# esp-node.net
KiCad netlist of a schematic drawn in Altium Designer
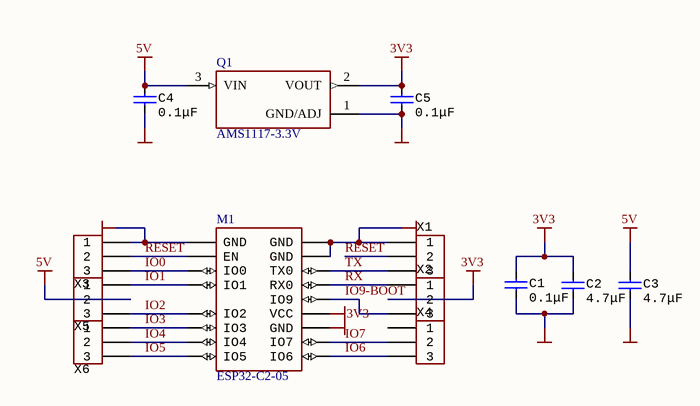
[diagram p0: esp-node.SchDoc]

(export (version "E")
  (design (tool "Eeschema 10.0.6"))
  (components
    (comp (ref "C1")
      (value "0.1μF")
      (footprint "CAP: 0603")
      (description "0.1uF, 100V, 0603, X7R, ±10%, -55...+125°C")
      (fields (field (name "MANUFACTURER") "Samsung") (field (name "PARTNUMBER") "CL10B104KC8NNNC"))
      (libsource (lib "capacitor") (part "CL10B104KC8NNNC"))
    )
    (comp (ref "C2")
      (value "4.7μF")
      (footprint "CAP: 0603")
      (description "4.7uF, 6.3V, 0603, X7R, ±20%, -55...+85°C")
      (fields (field (name "PARTNUMBER") "CL10B475KQ8NQNC") (field (name "MANUFACTURER") "Samsung"))
      (libsource (lib "capacitor") (part "CL10B475KQ8NQNC"))
    )
    (comp (ref "C3")
      (value "4.7μF")
      (footprint "CAP: 0603")
      (description "4.7uF, 6.3V, 0603, X7R, ±20%, -55...+85°C")
      (fields (field (name "PARTNUMBER") "CL10B475KQ8NQNC") (field (name "MANUFACTURER") "Samsung"))
      (libsource (lib "capacitor") (part "CL10B475KQ8NQNC"))
    )
    (comp (ref "C4")
      (value "0.1μF")
      (footprint "CAP: 0603")
      (description "0.1uF, 100V, 0603, X7R, ±10%, -55...+125°C")
      (fields (field (name "MANUFACTURER") "Samsung") (field (name "PARTNUMBER") "CL10B104KC8NNNC"))
      (libsource (lib "capacitor") (part "CL10B104KC8NNNC"))
    )
    (comp (ref "C5")
      (value "0.1μF")
      (footprint "CAP: 0603")
      (description "0.1uF, 100V, 0603, X7R, ±10%, -55...+125°C")
      (fields (field (name "MANUFACTURER") "Samsung") (field (name "PARTNUMBER") "CL10B104KC8NNNC"))
      (libsource (lib "capacitor") (part "CL10B104KC8NNNC"))
    )
    (comp (ref "M1")
      (value "ESP32-C2-05")
      (footprint "ESP32-C2-05")
      (libsource (lib "ic-mcu-dsp") (part "ESP32-C2-05"))
    )
    (comp (ref "Q1")
      (value "AMS1117-3.3V")
      (footprint "SOT223")
      (libsource (lib "ic-power-supply") (part "AMS1117-3.3V"))
    )
    (comp (ref "X1")
      (value "PMbus")
      (footprint "footprint:CON: PLS-3")
      (description "3 pins, pitch 2.54 mm, 500VAC, 2A/pin, -40...+85°C")
      (fields (field (name "MANUFACTURER") "Connfly") (field (name "PARTNUMBER") "PLS-3"))
      (libsource (lib "") (part "PLS-3_1"))
    )
    (comp (ref "X2")
      (value "PMbus")
      (footprint "footprint:CON: PLS-3")
      (description "3 pins, pitch 2.54 mm, 500VAC, 2A/pin, -40...+85°C")
      (fields (field (name "MANUFACTURER") "Connfly") (field (name "PARTNUMBER") "PLS-3"))
      (libsource (lib "") (part "PLS-3_1"))
    )
    (comp (ref "X3")
      (value "PMbus")
      (footprint "footprint:CON: PLS-3")
      (description "3 pins, pitch 2.54 mm, 500VAC, 2A/pin, -40...+85°C")
      (fields (field (name "MANUFACTURER") "Connfly") (field (name "PARTNUMBER") "PLS-3"))
      (libsource (lib "connector") (part "PLS-3"))
    )
    (comp (ref "X4")
      (value "PMbus")
      (footprint "footprint:CON: PLS-3")
      (description "3 pins, pitch 2.54 mm, 500VAC, 2A/pin, -40...+85°C")
      (fields (field (name "MANUFACTURER") "Connfly") (field (name "PARTNUMBER") "PLS-3"))
      (libsource (lib "") (part "PLS-3_1"))
    )
    (comp (ref "X5")
      (value "PMbus")
      (footprint "footprint:CON: PLS-3")
      (description "3 pins, pitch 2.54 mm, 500VAC, 2A/pin, -40...+85°C")
      (fields (field (name "MANUFACTURER") "Connfly") (field (name "PARTNUMBER") "PLS-3"))
      (libsource (lib "connector") (part "PLS-3"))
    )
    (comp (ref "X6")
      (value "PMbus")
      (footprint "footprint:CON: PLS-3")
      (description "3 pins, pitch 2.54 mm, 500VAC, 2A/pin, -40...+85°C")
      (fields (field (name "MANUFACTURER") "Connfly") (field (name "PARTNUMBER") "PLS-3"))
      (libsource (lib "connector") (part "PLS-3"))
    )
  )
  (nets
    (net (code "1") (name "/IO0") (class "Default")
      (node (ref "M1") (pin "3") (pinfunction "IO0_3") (pintype "bidirectional"))
      (node (ref "X3") (pin "3") (pinfunction "3_3") (pintype "power_in"))
    )
    (net (code "2") (name "/IO1") (class "Default")
      (node (ref "M1") (pin "4") (pinfunction "IO1_4") (pintype "bidirectional"))
      (node (ref "X5") (pin "1") (pinfunction "1_1") (pintype "passive"))
    )
    (net (code "3") (name "/IO2") (class "Default")
      (node (ref "M1") (pin "5") (pinfunction "IO2_5") (pintype "bidirectional"))
      (node (ref "X5") (pin "3") (pinfunction "3_3") (pintype "power_in"))
    )
    (net (code "4") (name "/IO3") (class "Default")
      (node (ref "M1") (pin "6") (pinfunction "IO3_6") (pintype "bidirectional"))
      (node (ref "X6") (pin "1") (pinfunction "1_1") (pintype "passive"))
    )
    (net (code "5") (name "/IO4") (class "Default")
      (node (ref "M1") (pin "7") (pinfunction "IO4_7") (pintype "bidirectional"))
      (node (ref "X6") (pin "2") (pinfunction "2_2") (pintype "passive"))
    )
    (net (code "6") (name "/IO5") (class "Default")
      (node (ref "M1") (pin "8") (pinfunction "IO5_8") (pintype "bidirectional"))
      (node (ref "X6") (pin "3") (pinfunction "3_3") (pintype "power_in"))
    )
    (net (code "7") (name "/IO6") (class "Default")
      (node (ref "M1") (pin "9") (pinfunction "IO6_9") (pintype "bidirectional"))
      (node (ref "X4") (pin "3") (pinfunction "3_3") (pintype "power_in"))
    )
    (net (code "8") (name "/IO7") (class "Default")
      (node (ref "M1") (pin "10") (pinfunction "IO7_10") (pintype "bidirectional"))
      (node (ref "X4") (pin "2") (pinfunction "2_2") (pintype "passive"))
    )
    (net (code "9") (name "/IO9-BOOT") (class "Default")
      (node (ref "M1") (pin "13") (pinfunction "IO9_13") (pintype "bidirectional"))
      (node (ref "X2") (pin "3") (pinfunction "3_3") (pintype "power_in"))
    )
    (net (code "10") (name "/RESET") (class "Default")
      (node (ref "M1") (pin "2") (pinfunction "EN_2") (pintype "passive"))
      (node (ref "X1") (pin "2") (pinfunction "2_2") (pintype "passive"))
      (node (ref "X3") (pin "2") (pinfunction "2_2") (pintype "passive"))
    )
    (net (code "11") (name "/RX") (class "Default")
      (node (ref "M1") (pin "14") (pinfunction "RX0_14") (pintype "bidirectional"))
      (node (ref "X2") (pin "1") (pinfunction "1_1") (pintype "passive"))
    )
    (net (code "12") (name "/TX") (class "Default")
      (node (ref "M1") (pin "15") (pinfunction "TX0_15") (pintype "bidirectional"))
      (node (ref "X1") (pin "3") (pinfunction "3_3") (pintype "power_in"))
    )
    (net (code "13") (name "3V3") (class "Default")
      (node (ref "C1") (pin "1") (pinfunction "1_1") (pintype "passive"))
      (node (ref "C2") (pin "1") (pinfunction "1_1") (pintype "passive"))
      (node (ref "C5") (pin "1") (pinfunction "1_1") (pintype "passive"))
      (node (ref "M1") (pin "12") (pinfunction "VCC_12") (pintype "passive"))
      (node (ref "Q1") (pin "2") (pinfunction "VOUT_2") (pintype "output"))
      (node (ref "X2") (pin "2") (pinfunction "2_2") (pintype "passive"))
    )
    (net (code "14") (name "5V") (class "Default")
      (node (ref "C3") (pin "1") (pinfunction "1_1") (pintype "passive"))
      (node (ref "C4") (pin "1") (pinfunction "1_1") (pintype "passive"))
      (node (ref "Q1") (pin "3") (pinfunction "VIN_3") (pintype "input"))
      (node (ref "X5") (pin "2") (pinfunction "2_2") (pintype "passive"))
    )
    (net (code "15") (name "GND") (class "Default")
      (node (ref "C1") (pin "2") (pinfunction "2_2") (pintype "passive"))
      (node (ref "C2") (pin "2") (pinfunction "2_2") (pintype "passive"))
      (node (ref "C3") (pin "2") (pinfunction "2_2") (pintype "passive"))
      (node (ref "C4") (pin "2") (pinfunction "2_2") (pintype "passive"))
      (node (ref "C5") (pin "2") (pinfunction "2_2") (pintype "passive"))
      (node (ref "M1") (pin "1") (pinfunction "GND_1") (pintype "passive"))
      (node (ref "M1") (pin "11") (pinfunction "GND_11") (pintype "passive"))
      (node (ref "M1") (pin "16") (pinfunction "GND_16") (pintype "passive"))
      (node (ref "M1") (pin "17") (pinfunction "GND_17") (pintype "passive"))
      (node (ref "Q1") (pin "1") (pinfunction "GND/ADJ_1") (pintype "power_in"))
      (node (ref "X1") (pin "1") (pinfunction "1_1") (pintype "passive"))
      (node (ref "X3") (pin "1") (pinfunction "1_1") (pintype "passive"))
    )
    (net (code "16") (name "unconnected-(X4-Pad1)") (class "Default")
      (node (ref "X4") (pin "1") (pinfunction "1_1") (pintype "passive"))
    )
  )
)
